# PIN-HEADERS.net
KiCad netlist of a schematic drawn in Altium Designer
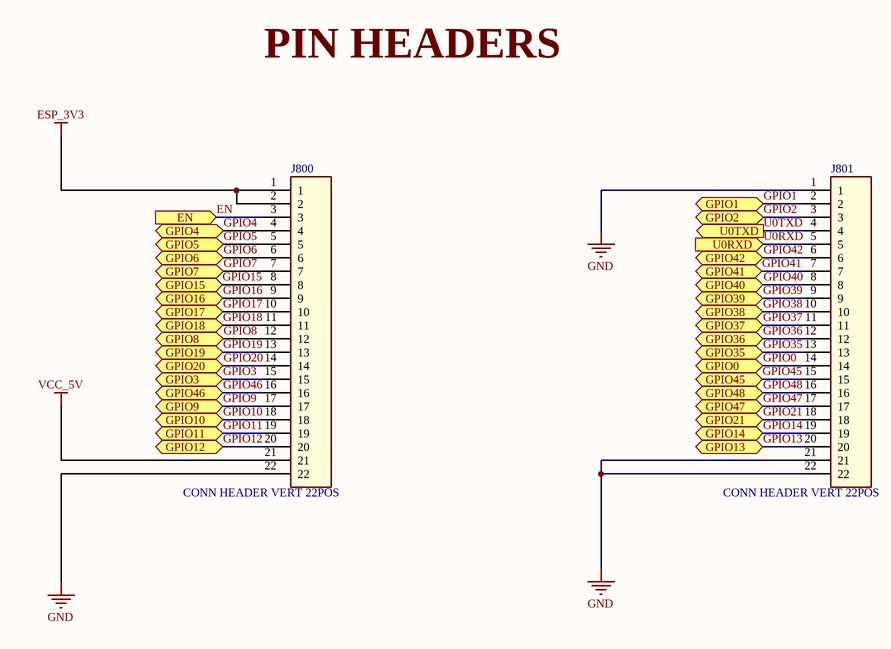
[diagram p0: PIN-HEADERS.SchDoc]

(export (version "E")
  (design (tool "Eeschema 10.0.6"))
  (components
    (comp (ref "J800")
      (value "CONN HEADER VERT 22POS")
      (footprint "CON22_1X22_TU_TSW")
      (description "Connector Header Through Hole 22 position 0.100\" (2.54mm)")
      (libsource (lib "ESP32_Integrated_Library") (part "TSW-122-08-T-S"))
    )
    (comp (ref "J801")
      (value "CONN HEADER VERT 22POS")
      (footprint "CON22_1X22_TU_TSW")
      (description "Connector Header Through Hole 22 position 0.100\" (2.54mm)")
      (libsource (lib "ESP32_Integrated_Library") (part "TSW-122-08-T-S"))
    )
  )
  (nets
    (net (code "1") (name "/EN") (class "Default")
      (node (ref "J800") (pin "3") (pinfunction "3_3") (pintype "passive"))
    )
    (net (code "2") (name "/GPIO0") (class "Default")
      (node (ref "J801") (pin "14") (pinfunction "14_14") (pintype "passive"))
    )
    (net (code "3") (name "/GPIO1") (class "Default")
      (node (ref "J801") (pin "2") (pinfunction "2_2") (pintype "passive"))
    )
    (net (code "4") (name "/GPIO2") (class "Default")
      (node (ref "J801") (pin "3") (pinfunction "3_3") (pintype "passive"))
    )
    (net (code "5") (name "/GPIO3") (class "Default")
      (node (ref "J800") (pin "15") (pinfunction "15_15") (pintype "passive"))
    )
    (net (code "6") (name "/GPIO4") (class "Default")
      (node (ref "J800") (pin "4") (pinfunction "4_4") (pintype "passive"))
    )
    (net (code "7") (name "/GPIO5") (class "Default")
      (node (ref "J800") (pin "5") (pinfunction "5_5") (pintype "passive"))
    )
    (net (code "8") (name "/GPIO6") (class "Default")
      (node (ref "J800") (pin "6") (pinfunction "6_6") (pintype "passive"))
    )
    (net (code "9") (name "/GPIO7") (class "Default")
      (node (ref "J800") (pin "7") (pinfunction "7_7") (pintype "passive"))
    )
    (net (code "10") (name "/GPIO8") (class "Default")
      (node (ref "J800") (pin "12") (pinfunction "12_12") (pintype "passive"))
    )
    (net (code "11") (name "/GPIO9") (class "Default")
      (node (ref "J800") (pin "17") (pinfunction "17_17") (pintype "passive"))
    )
    (net (code "12") (name "/GPIO10") (class "Default")
      (node (ref "J800") (pin "18") (pinfunction "18_18") (pintype "passive"))
    )
    (net (code "13") (name "/GPIO11") (class "Default")
      (node (ref "J800") (pin "19") (pinfunction "19_19") (pintype "passive"))
    )
    (net (code "14") (name "/GPIO12") (class "Default")
      (node (ref "J800") (pin "20") (pinfunction "20_20") (pintype "passive"))
    )
    (net (code "15") (name "/GPIO13") (class "Default")
      (node (ref "J801") (pin "20") (pinfunction "20_20") (pintype "passive"))
    )
    (net (code "16") (name "/GPIO14") (class "Default")
      (node (ref "J801") (pin "19") (pinfunction "19_19") (pintype "passive"))
    )
    (net (code "17") (name "/GPIO15") (class "Default")
      (node (ref "J800") (pin "8") (pinfunction "8_8") (pintype "passive"))
    )
    (net (code "18") (name "/GPIO16") (class "Default")
      (node (ref "J800") (pin "9") (pinfunction "9_9") (pintype "passive"))
    )
    (net (code "19") (name "/GPIO17") (class "Default")
      (node (ref "J800") (pin "10") (pinfunction "10_10") (pintype "passive"))
    )
    (net (code "20") (name "/GPIO18") (class "Default")
      (node (ref "J800") (pin "11") (pinfunction "11_11") (pintype "passive"))
    )
    (net (code "21") (name "/GPIO19") (class "Default")
      (node (ref "J800") (pin "13") (pinfunction "13_13") (pintype "passive"))
    )
    (net (code "22") (name "/GPIO20") (class "Default")
      (node (ref "J800") (pin "14") (pinfunction "14_14") (pintype "passive"))
    )
    (net (code "23") (name "/GPIO21") (class "Default")
      (node (ref "J801") (pin "18") (pinfunction "18_18") (pintype "passive"))
    )
    (net (code "24") (name "/GPIO35") (class "Default")
      (node (ref "J801") (pin "13") (pinfunction "13_13") (pintype "passive"))
    )
    (net (code "25") (name "/GPIO36") (class "Default")
      (node (ref "J801") (pin "12") (pinfunction "12_12") (pintype "passive"))
    )
    (net (code "26") (name "/GPIO37") (class "Default")
      (node (ref "J801") (pin "11") (pinfunction "11_11") (pintype "passive"))
    )
    (net (code "27") (name "/GPIO38") (class "Default")
      (node (ref "J801") (pin "10") (pinfunction "10_10") (pintype "passive"))
    )
    (net (code "28") (name "/GPIO39") (class "Default")
      (node (ref "J801") (pin "9") (pinfunction "9_9") (pintype "passive"))
    )
    (net (code "29") (name "/GPIO40") (class "Default")
      (node (ref "J801") (pin "8") (pinfunction "8_8") (pintype "passive"))
    )
    (net (code "30") (name "/GPIO41") (class "Default")
      (node (ref "J801") (pin "7") (pinfunction "7_7") (pintype "passive"))
    )
    (net (code "31") (name "/GPIO42") (class "Default")
      (node (ref "J801") (pin "6") (pinfunction "6_6") (pintype "passive"))
    )
    (net (code "32") (name "/GPIO45") (class "Default")
      (node (ref "J801") (pin "15") (pinfunction "15_15") (pintype "passive"))
    )
    (net (code "33") (name "/GPIO46") (class "Default")
      (node (ref "J800") (pin "16") (pinfunction "16_16") (pintype "passive"))
    )
    (net (code "34") (name "/GPIO47") (class "Default")
      (node (ref "J801") (pin "17") (pinfunction "17_17") (pintype "passive"))
    )
    (net (code "35") (name "/GPIO48") (class "Default")
      (node (ref "J801") (pin "16") (pinfunction "16_16") (pintype "passive"))
    )
    (net (code "36") (name "/U0RXD") (class "Default")
      (node (ref "J801") (pin "5") (pinfunction "5_5") (pintype "passive"))
    )
    (net (code "37") (name "/U0TXD") (class "Default")
      (node (ref "J801") (pin "4") (pinfunction "4_4") (pintype "passive"))
    )
    (net (code "38") (name "ESP_3V3") (class "Default")
      (node (ref "J800") (pin "1") (pinfunction "1_1") (pintype "passive"))
      (node (ref "J800") (pin "2") (pinfunction "2_2") (pintype "passive"))
    )
    (net (code "39") (name "GND") (class "Default")
      (node (ref "J800") (pin "22") (pinfunction "22_22") (pintype "passive"))
      (node (ref "J801") (pin "1") (pinfunction "1_1") (pintype "passive"))
      (node (ref "J801") (pin "21") (pinfunction "21_21") (pintype "passive"))
      (node (ref "J801") (pin "22") (pinfunction "22_22") (pintype "passive"))
    )
    (net (code "40") (name "VCC_5V") (class "Default")
      (node (ref "J800") (pin "21") (pinfunction "21_21") (pintype "passive"))
    )
  )
)
